# 16_ch_sample-and-hold_card_-_2.net
KiCad netlist of a schematic drawn in EAGLE
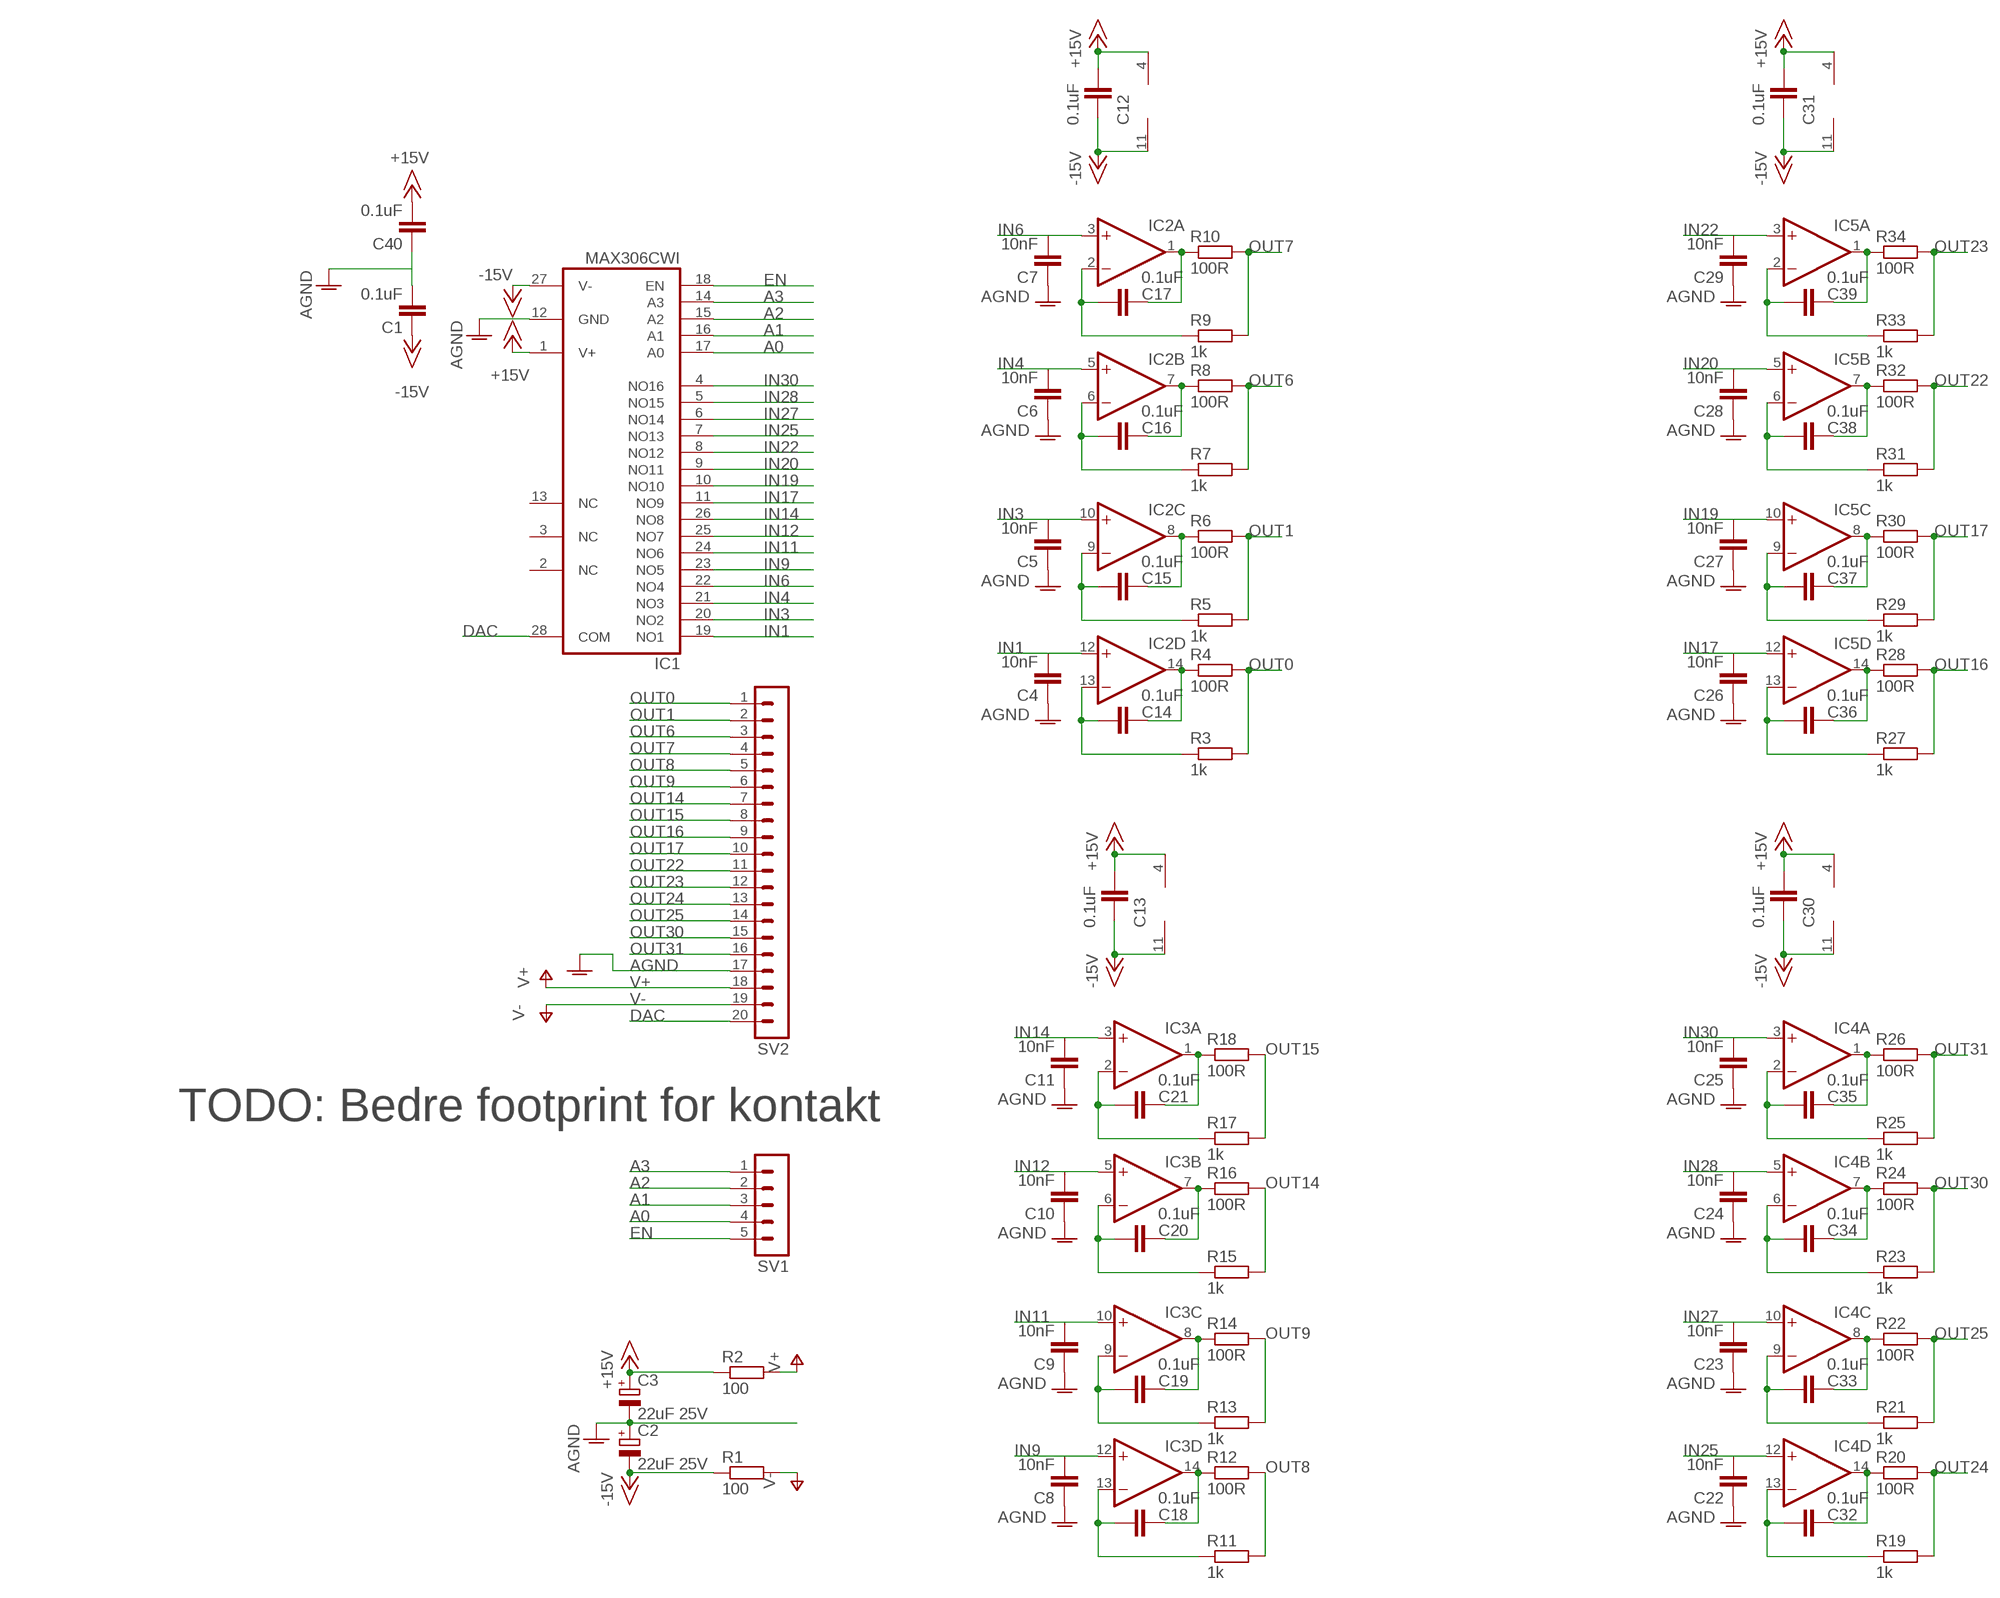
[diagram p0: schematic, sheet 1]

(export (version "E")
  (design (tool "Eeschema 10.0.6"))
  (components
    (comp (ref "C1")
      (value "0.1uF")
      (footprint "eagle-import:C0603")
      (libsource (lib "eagle-import") (part "C-EUC0603"))
    )
    (comp (ref "C2")
      (value "22uF 25V")
      (footprint "eagle-import:E2-5")
      (libsource (lib "eagle-import") (part "CPOL-EUE2-5"))
    )
    (comp (ref "C3")
      (value "22uF 25V")
      (footprint "eagle-import:E2-5")
      (libsource (lib "eagle-import") (part "CPOL-EUE2-5"))
    )
    (comp (ref "C4")
      (value "10nF")
      (footprint "eagle-import:C1206")
      (libsource (lib "eagle-import") (part "C-EUC1206"))
    )
    (comp (ref "C5")
      (value "10nF")
      (footprint "eagle-import:C1206")
      (libsource (lib "eagle-import") (part "C-EUC1206"))
    )
    (comp (ref "C6")
      (value "10nF")
      (footprint "eagle-import:C1206")
      (libsource (lib "eagle-import") (part "C-EUC1206"))
    )
    (comp (ref "C7")
      (value "10nF")
      (footprint "eagle-import:C1206")
      (libsource (lib "eagle-import") (part "C-EUC1206"))
    )
    (comp (ref "C8")
      (value "10nF")
      (footprint "eagle-import:C1206")
      (libsource (lib "eagle-import") (part "C-EUC1206"))
    )
    (comp (ref "C9")
      (value "10nF")
      (footprint "eagle-import:C1206")
      (libsource (lib "eagle-import") (part "C-EUC1206"))
    )
    (comp (ref "C10")
      (value "10nF")
      (footprint "eagle-import:C1206")
      (libsource (lib "eagle-import") (part "C-EUC1206"))
    )
    (comp (ref "C11")
      (value "10nF")
      (footprint "eagle-import:C1206")
      (libsource (lib "eagle-import") (part "C-EUC1206"))
    )
    (comp (ref "C12")
      (value "0.1uF")
      (footprint "eagle-import:C0603")
      (libsource (lib "eagle-import") (part "C-EUC0603"))
    )
    (comp (ref "C13")
      (value "0.1uF")
      (footprint "eagle-import:C0603")
      (libsource (lib "eagle-import") (part "C-EUC0603"))
    )
    (comp (ref "C14")
      (value "0.1uF")
      (footprint "eagle-import:C0603")
      (libsource (lib "eagle-import") (part "C-EUC0603"))
    )
    (comp (ref "C15")
      (value "0.1uF")
      (footprint "eagle-import:C0603")
      (libsource (lib "eagle-import") (part "C-EUC0603"))
    )
    (comp (ref "C16")
      (value "0.1uF")
      (footprint "eagle-import:C0603")
      (libsource (lib "eagle-import") (part "C-EUC0603"))
    )
    (comp (ref "C17")
      (value "0.1uF")
      (footprint "eagle-import:C0603")
      (libsource (lib "eagle-import") (part "C-EUC0603"))
    )
    (comp (ref "C18")
      (value "0.1uF")
      (footprint "eagle-import:C0603")
      (libsource (lib "eagle-import") (part "C-EUC0603"))
    )
    (comp (ref "C19")
      (value "0.1uF")
      (footprint "eagle-import:C0603")
      (libsource (lib "eagle-import") (part "C-EUC0603"))
    )
    (comp (ref "C20")
      (value "0.1uF")
      (footprint "eagle-import:C0603")
      (libsource (lib "eagle-import") (part "C-EUC0603"))
    )
    (comp (ref "C21")
      (value "0.1uF")
      (footprint "eagle-import:C0603")
      (libsource (lib "eagle-import") (part "C-EUC0603"))
    )
    (comp (ref "C22")
      (value "10nF")
      (footprint "eagle-import:C1206")
      (libsource (lib "eagle-import") (part "C-EUC1206"))
    )
    (comp (ref "C23")
      (value "10nF")
      (footprint "eagle-import:C1206")
      (libsource (lib "eagle-import") (part "C-EUC1206"))
    )
    (comp (ref "C24")
      (value "10nF")
      (footprint "eagle-import:C1206")
      (libsource (lib "eagle-import") (part "C-EUC1206"))
    )
    (comp (ref "C25")
      (value "10nF")
      (footprint "eagle-import:C1206")
      (libsource (lib "eagle-import") (part "C-EUC1206"))
    )
    (comp (ref "C26")
      (value "10nF")
      (footprint "eagle-import:C1206")
      (libsource (lib "eagle-import") (part "C-EUC1206"))
    )
    (comp (ref "C27")
      (value "10nF")
      (footprint "eagle-import:C1206")
      (libsource (lib "eagle-import") (part "C-EUC1206"))
    )
    (comp (ref "C28")
      (value "10nF")
      (footprint "eagle-import:C1206")
      (libsource (lib "eagle-import") (part "C-EUC1206"))
    )
    (comp (ref "C29")
      (value "10nF")
      (footprint "eagle-import:C1206")
      (libsource (lib "eagle-import") (part "C-EUC1206"))
    )
    (comp (ref "C30")
      (value "0.1uF")
      (footprint "eagle-import:C0603")
      (libsource (lib "eagle-import") (part "C-EUC0603"))
    )
    (comp (ref "C31")
      (value "0.1uF")
      (footprint "eagle-import:C0603")
      (libsource (lib "eagle-import") (part "C-EUC0603"))
    )
    (comp (ref "C32")
      (value "0.1uF")
      (footprint "eagle-import:C0603")
      (libsource (lib "eagle-import") (part "C-EUC0603"))
    )
    (comp (ref "C33")
      (value "0.1uF")
      (footprint "eagle-import:C0603")
      (libsource (lib "eagle-import") (part "C-EUC0603"))
    )
    (comp (ref "C34")
      (value "0.1uF")
      (footprint "eagle-import:C0603")
      (libsource (lib "eagle-import") (part "C-EUC0603"))
    )
    (comp (ref "C35")
      (value "0.1uF")
      (footprint "eagle-import:C0603")
      (libsource (lib "eagle-import") (part "C-EUC0603"))
    )
    (comp (ref "C36")
      (value "0.1uF")
      (footprint "eagle-import:C0603")
      (libsource (lib "eagle-import") (part "C-EUC0603"))
    )
    (comp (ref "C37")
      (value "0.1uF")
      (footprint "eagle-import:C0603")
      (libsource (lib "eagle-import") (part "C-EUC0603"))
    )
    (comp (ref "C38")
      (value "0.1uF")
      (footprint "eagle-import:C0603")
      (libsource (lib "eagle-import") (part "C-EUC0603"))
    )
    (comp (ref "C39")
      (value "0.1uF")
      (footprint "eagle-import:C0603")
      (libsource (lib "eagle-import") (part "C-EUC0603"))
    )
    (comp (ref "C40")
      (value "0.1uF")
      (footprint "eagle-import:C0603")
      (libsource (lib "eagle-import") (part "C-EUC0603"))
    )
    (comp (ref "IC1")
      (value "MAX306CWI")
      (footprint "eagle-import:SO28L")
      (fields (field (name "MF") "MAXIM"))
      (libsource (lib "eagle-import") (part "MAX306CWI"))
    )
    (comp (ref "IC2")
      (value "TL074D")
      (footprint "eagle-import:SO14")
      (libsource (lib "eagle-import") (part "TL074D"))
    )
    (comp (ref "IC3")
      (value "TL074D")
      (footprint "eagle-import:SO14")
      (libsource (lib "eagle-import") (part "TL074D"))
    )
    (comp (ref "IC4")
      (value "TL074D")
      (footprint "eagle-import:SO14")
      (libsource (lib "eagle-import") (part "TL074D"))
    )
    (comp (ref "IC5")
      (value "TL074D")
      (footprint "eagle-import:SO14")
      (libsource (lib "eagle-import") (part "TL074D"))
    )
    (comp (ref "R1")
      (value "100")
      (footprint "eagle-import:0207_7")
      (libsource (lib "eagle-import") (part "R-EU_0207/7"))
    )
    (comp (ref "R2")
      (value "100")
      (footprint "eagle-import:0207_7")
      (libsource (lib "eagle-import") (part "R-EU_0207/7"))
    )
    (comp (ref "R3")
      (value "1k")
      (footprint "eagle-import:R0603")
      (libsource (lib "eagle-import") (part "R-EU_R0603"))
    )
    (comp (ref "R4")
      (value "100R")
      (footprint "eagle-import:R0603")
      (libsource (lib "eagle-import") (part "R-EU_R0603"))
    )
    (comp (ref "R5")
      (value "1k")
      (footprint "eagle-import:R0603")
      (libsource (lib "eagle-import") (part "R-EU_R0603"))
    )
    (comp (ref "R6")
      (value "100R")
      (footprint "eagle-import:R0603")
      (libsource (lib "eagle-import") (part "R-EU_R0603"))
    )
    (comp (ref "R7")
      (value "1k")
      (footprint "eagle-import:R0603")
      (libsource (lib "eagle-import") (part "R-EU_R0603"))
    )
    (comp (ref "R8")
      (value "100R")
      (footprint "eagle-import:R0603")
      (libsource (lib "eagle-import") (part "R-EU_R0603"))
    )
    (comp (ref "R9")
      (value "1k")
      (footprint "eagle-import:R0603")
      (libsource (lib "eagle-import") (part "R-EU_R0603"))
    )
    (comp (ref "R10")
      (value "100R")
      (footprint "eagle-import:R0603")
      (libsource (lib "eagle-import") (part "R-EU_R0603"))
    )
    (comp (ref "R11")
      (value "1k")
      (footprint "eagle-import:R0603")
      (libsource (lib "eagle-import") (part "R-EU_R0603"))
    )
    (comp (ref "R12")
      (value "100R")
      (footprint "eagle-import:R0603")
      (libsource (lib "eagle-import") (part "R-EU_R0603"))
    )
    (comp (ref "R13")
      (value "1k")
      (footprint "eagle-import:R0603")
      (libsource (lib "eagle-import") (part "R-EU_R0603"))
    )
    (comp (ref "R14")
      (value "100R")
      (footprint "eagle-import:R0603")
      (libsource (lib "eagle-import") (part "R-EU_R0603"))
    )
    (comp (ref "R15")
      (value "1k")
      (footprint "eagle-import:R0603")
      (libsource (lib "eagle-import") (part "R-EU_R0603"))
    )
    (comp (ref "R16")
      (value "100R")
      (footprint "eagle-import:R0603")
      (libsource (lib "eagle-import") (part "R-EU_R0603"))
    )
    (comp (ref "R17")
      (value "1k")
      (footprint "eagle-import:R0603")
      (libsource (lib "eagle-import") (part "R-EU_R0603"))
    )
    (comp (ref "R18")
      (value "100R")
      (footprint "eagle-import:R0603")
      (libsource (lib "eagle-import") (part "R-EU_R0603"))
    )
    (comp (ref "R19")
      (value "1k")
      (footprint "eagle-import:R0603")
      (libsource (lib "eagle-import") (part "R-EU_R0603"))
    )
    (comp (ref "R20")
      (value "100R")
      (footprint "eagle-import:R0603")
      (libsource (lib "eagle-import") (part "R-EU_R0603"))
    )
    (comp (ref "R21")
      (value "1k")
      (footprint "eagle-import:R0603")
      (libsource (lib "eagle-import") (part "R-EU_R0603"))
    )
    (comp (ref "R22")
      (value "100R")
      (footprint "eagle-import:R0603")
      (libsource (lib "eagle-import") (part "R-EU_R0603"))
    )
    (comp (ref "R23")
      (value "1k")
      (footprint "eagle-import:R0603")
      (libsource (lib "eagle-import") (part "R-EU_R0603"))
    )
    (comp (ref "R24")
      (value "100R")
      (footprint "eagle-import:R0603")
      (libsource (lib "eagle-import") (part "R-EU_R0603"))
    )
    (comp (ref "R25")
      (value "1k")
      (footprint "eagle-import:R0603")
      (libsource (lib "eagle-import") (part "R-EU_R0603"))
    )
    (comp (ref "R26")
      (value "100R")
      (footprint "eagle-import:R0603")
      (libsource (lib "eagle-import") (part "R-EU_R0603"))
    )
    (comp (ref "R27")
      (value "1k")
      (footprint "eagle-import:R0603")
      (libsource (lib "eagle-import") (part "R-EU_R0603"))
    )
    (comp (ref "R28")
      (value "100R")
      (footprint "eagle-import:R0603")
      (libsource (lib "eagle-import") (part "R-EU_R0603"))
    )
    (comp (ref "R29")
      (value "1k")
      (footprint "eagle-import:R0603")
      (libsource (lib "eagle-import") (part "R-EU_R0603"))
    )
    (comp (ref "R30")
      (value "100R")
      (footprint "eagle-import:R0603")
      (libsource (lib "eagle-import") (part "R-EU_R0603"))
    )
    (comp (ref "R31")
      (value "1k")
      (footprint "eagle-import:R0603")
      (libsource (lib "eagle-import") (part "R-EU_R0603"))
    )
    (comp (ref "R32")
      (value "100R")
      (footprint "eagle-import:R0603")
      (libsource (lib "eagle-import") (part "R-EU_R0603"))
    )
    (comp (ref "R33")
      (value "1k")
      (footprint "eagle-import:R0603")
      (libsource (lib "eagle-import") (part "R-EU_R0603"))
    )
    (comp (ref "R34")
      (value "100R")
      (footprint "eagle-import:R0603")
      (libsource (lib "eagle-import") (part "R-EU_R0603"))
    )
    (comp (ref "SV1")
      (value "MA05-1")
      (footprint "eagle-import:MA05-1")
      (libsource (lib "eagle-import") (part "MA05-1"))
    )
    (comp (ref "SV2")
      (value "MA20-1")
      (footprint "eagle-import:MA20-1")
      (libsource (lib "eagle-import") (part "MA20-1"))
    )
  )
  (nets
    (net (code "1") (name "+15V") (class "Default")
      (node (ref "C12") (pin "1") (pinfunction "1_1") (pintype "passive"))
      (node (ref "C13") (pin "1") (pinfunction "1_1") (pintype "passive"))
      (node (ref "C3") (pin "+") (pinfunction "+_+") (pintype "passive"))
      (node (ref "C30") (pin "1") (pinfunction "1_1") (pintype "passive"))
      (node (ref "C31") (pin "1") (pinfunction "1_1") (pintype "passive"))
      (node (ref "C40") (pin "2") (pinfunction "2_2") (pintype "passive"))
      (node (ref "IC1") (pin "1") (pinfunction "V+_1") (pintype "power_in"))
      (node (ref "IC2") (pin "4") (pinfunction "V+_4") (pintype "power_in"))
      (node (ref "IC3") (pin "4") (pinfunction "V+_4") (pintype "power_in"))
      (node (ref "IC4") (pin "4") (pinfunction "V+_4") (pintype "power_in"))
      (node (ref "IC5") (pin "4") (pinfunction "V+_4") (pintype "power_in"))
      (node (ref "R2") (pin "1") (pinfunction "1_1") (pintype "passive"))
    )
    (net (code "2") (name "-15V") (class "Default")
      (node (ref "C1") (pin "1") (pinfunction "1_1") (pintype "passive"))
      (node (ref "C12") (pin "2") (pinfunction "2_2") (pintype "passive"))
      (node (ref "C13") (pin "2") (pinfunction "2_2") (pintype "passive"))
      (node (ref "C2") (pin "-") (pinfunction "-_-") (pintype "passive"))
      (node (ref "C30") (pin "2") (pinfunction "2_2") (pintype "passive"))
      (node (ref "C31") (pin "2") (pinfunction "2_2") (pintype "passive"))
      (node (ref "IC1") (pin "27") (pinfunction "V-_27") (pintype "power_in"))
      (node (ref "IC2") (pin "11") (pinfunction "V-_11") (pintype "power_in"))
      (node (ref "IC3") (pin "11") (pinfunction "V-_11") (pintype "power_in"))
      (node (ref "IC4") (pin "11") (pinfunction "V-_11") (pintype "power_in"))
      (node (ref "IC5") (pin "11") (pinfunction "V-_11") (pintype "power_in"))
      (node (ref "R1") (pin "1") (pinfunction "1_1") (pintype "passive"))
    )
    (net (code "3") (name "/A0") (class "Default")
      (node (ref "IC1") (pin "17") (pinfunction "A0_17") (pintype "input"))
      (node (ref "SV1") (pin "4") (pinfunction "4_4") (pintype "passive"))
    )
    (net (code "4") (name "/A1") (class "Default")
      (node (ref "IC1") (pin "16") (pinfunction "A1_16") (pintype "input"))
      (node (ref "SV1") (pin "3") (pinfunction "3_3") (pintype "passive"))
    )
    (net (code "5") (name "/A2") (class "Default")
      (node (ref "IC1") (pin "15") (pinfunction "A2_15") (pintype "input"))
      (node (ref "SV1") (pin "2") (pinfunction "2_2") (pintype "passive"))
    )
    (net (code "6") (name "/A3") (class "Default")
      (node (ref "IC1") (pin "14") (pinfunction "A3_14") (pintype "input"))
      (node (ref "SV1") (pin "1") (pinfunction "1_1") (pintype "passive"))
    )
    (net (code "7") (name "/DAC") (class "Default")
      (node (ref "IC1") (pin "28") (pinfunction "COM_28") (pintype "passive"))
      (node (ref "SV2") (pin "20") (pinfunction "20_20") (pintype "passive"))
    )
    (net (code "8") (name "/EN") (class "Default")
      (node (ref "IC1") (pin "18") (pinfunction "EN_18") (pintype "input"))
      (node (ref "SV1") (pin "5") (pinfunction "5_5") (pintype "passive"))
    )
    (net (code "9") (name "/IN1") (class "Default")
      (node (ref "C4") (pin "2") (pinfunction "2_2") (pintype "passive"))
      (node (ref "IC1") (pin "19") (pinfunction "NO1_19") (pintype "passive"))
      (node (ref "IC2") (pin "12") (pinfunction "+IN_12") (pintype "input"))
    )
    (net (code "10") (name "/IN3") (class "Default")
      (node (ref "C5") (pin "2") (pinfunction "2_2") (pintype "passive"))
      (node (ref "IC1") (pin "20") (pinfunction "NO2_20") (pintype "passive"))
      (node (ref "IC2") (pin "10") (pinfunction "+IN_10") (pintype "input"))
    )
    (net (code "11") (name "/IN4") (class "Default")
      (node (ref "C6") (pin "2") (pinfunction "2_2") (pintype "passive"))
      (node (ref "IC1") (pin "21") (pinfunction "NO3_21") (pintype "passive"))
      (node (ref "IC2") (pin "5") (pinfunction "+IN_5") (pintype "input"))
    )
    (net (code "12") (name "/IN6") (class "Default")
      (node (ref "C7") (pin "2") (pinfunction "2_2") (pintype "passive"))
      (node (ref "IC1") (pin "22") (pinfunction "NO4_22") (pintype "passive"))
      (node (ref "IC2") (pin "3") (pinfunction "+IN_3") (pintype "input"))
    )
    (net (code "13") (name "/IN9") (class "Default")
      (node (ref "C8") (pin "2") (pinfunction "2_2") (pintype "passive"))
      (node (ref "IC1") (pin "23") (pinfunction "NO5_23") (pintype "passive"))
      (node (ref "IC3") (pin "12") (pinfunction "+IN_12") (pintype "input"))
    )
    (net (code "14") (name "/IN11") (class "Default")
      (node (ref "C9") (pin "2") (pinfunction "2_2") (pintype "passive"))
      (node (ref "IC1") (pin "24") (pinfunction "NO6_24") (pintype "passive"))
      (node (ref "IC3") (pin "10") (pinfunction "+IN_10") (pintype "input"))
    )
    (net (code "15") (name "/IN12") (class "Default")
      (node (ref "C10") (pin "2") (pinfunction "2_2") (pintype "passive"))
      (node (ref "IC1") (pin "25") (pinfunction "NO7_25") (pintype "passive"))
      (node (ref "IC3") (pin "5") (pinfunction "+IN_5") (pintype "input"))
    )
    (net (code "16") (name "/IN14") (class "Default")
      (node (ref "C11") (pin "2") (pinfunction "2_2") (pintype "passive"))
      (node (ref "IC1") (pin "26") (pinfunction "NO8_26") (pintype "passive"))
      (node (ref "IC3") (pin "3") (pinfunction "+IN_3") (pintype "input"))
    )
    (net (code "17") (name "/IN17") (class "Default")
      (node (ref "C26") (pin "2") (pinfunction "2_2") (pintype "passive"))
      (node (ref "IC1") (pin "11") (pinfunction "NO9_11") (pintype "passive"))
      (node (ref "IC5") (pin "12") (pinfunction "+IN_12") (pintype "input"))
    )
    (net (code "18") (name "/IN19") (class "Default")
      (node (ref "C27") (pin "2") (pinfunction "2_2") (pintype "passive"))
      (node (ref "IC1") (pin "10") (pinfunction "NO10_10") (pintype "passive"))
      (node (ref "IC5") (pin "10") (pinfunction "+IN_10") (pintype "input"))
    )
    (net (code "19") (name "/IN20") (class "Default")
      (node (ref "C28") (pin "2") (pinfunction "2_2") (pintype "passive"))
      (node (ref "IC1") (pin "9") (pinfunction "NO11_9") (pintype "passive"))
      (node (ref "IC5") (pin "5") (pinfunction "+IN_5") (pintype "input"))
    )
    (net (code "20") (name "/IN22") (class "Default")
      (node (ref "C29") (pin "2") (pinfunction "2_2") (pintype "passive"))
      (node (ref "IC1") (pin "8") (pinfunction "NO12_8") (pintype "passive"))
      (node (ref "IC5") (pin "3") (pinfunction "+IN_3") (pintype "input"))
    )
    (net (code "21") (name "/IN25") (class "Default")
      (node (ref "C22") (pin "2") (pinfunction "2_2") (pintype "passive"))
      (node (ref "IC1") (pin "7") (pinfunction "NO13_7") (pintype "passive"))
      (node (ref "IC4") (pin "12") (pinfunction "+IN_12") (pintype "input"))
    )
    (net (code "22") (name "/IN27") (class "Default")
      (node (ref "C23") (pin "2") (pinfunction "2_2") (pintype "passive"))
      (node (ref "IC1") (pin "6") (pinfunction "NO14_6") (pintype "passive"))
      (node (ref "IC4") (pin "10") (pinfunction "+IN_10") (pintype "input"))
    )
    (net (code "23") (name "/IN28") (class "Default")
      (node (ref "C24") (pin "2") (pinfunction "2_2") (pintype "passive"))
      (node (ref "IC1") (pin "5") (pinfunction "NO15_5") (pintype "passive"))
      (node (ref "IC4") (pin "5") (pinfunction "+IN_5") (pintype "input"))
    )
    (net (code "24") (name "/IN30") (class "Default")
      (node (ref "C25") (pin "2") (pinfunction "2_2") (pintype "passive"))
      (node (ref "IC1") (pin "4") (pinfunction "NO16_4") (pintype "passive"))
      (node (ref "IC4") (pin "3") (pinfunction "+IN_3") (pintype "input"))
    )
    (net (code "25") (name "/OUT0") (class "Default")
      (node (ref "R3") (pin "2") (pinfunction "2_2") (pintype "passive"))
      (node (ref "R4") (pin "2") (pinfunction "2_2") (pintype "passive"))
      (node (ref "SV2") (pin "1") (pinfunction "1_1") (pintype "passive"))
    )
    (net (code "26") (name "/OUT1") (class "Default")
      (node (ref "R5") (pin "2") (pinfunction "2_2") (pintype "passive"))
      (node (ref "R6") (pin "2") (pinfunction "2_2") (pintype "passive"))
      (node (ref "SV2") (pin "2") (pinfunction "2_2") (pintype "passive"))
    )
    (net (code "27") (name "/OUT6") (class "Default")
      (node (ref "R7") (pin "2") (pinfunction "2_2") (pintype "passive"))
      (node (ref "R8") (pin "2") (pinfunction "2_2") (pintype "passive"))
      (node (ref "SV2") (pin "3") (pinfunction "3_3") (pintype "passive"))
    )
    (net (code "28") (name "/OUT7") (class "Default")
      (node (ref "R10") (pin "2") (pinfunction "2_2") (pintype "passive"))
      (node (ref "R9") (pin "2") (pinfunction "2_2") (pintype "passive"))
      (node (ref "SV2") (pin "4") (pinfunction "4_4") (pintype "passive"))
    )
    (net (code "29") (name "/OUT8") (class "Default")
      (node (ref "R11") (pin "2") (pinfunction "2_2") (pintype "passive"))
      (node (ref "R12") (pin "2") (pinfunction "2_2") (pintype "passive"))
      (node (ref "SV2") (pin "5") (pinfunction "5_5") (pintype "passive"))
    )
    (net (code "30") (name "/OUT9") (class "Default")
      (node (ref "R13") (pin "2") (pinfunction "2_2") (pintype "passive"))
      (node (ref "R14") (pin "2") (pinfunction "2_2") (pintype "passive"))
      (node (ref "SV2") (pin "6") (pinfunction "6_6") (pintype "passive"))
    )
    (net (code "31") (name "/OUT14") (class "Default")
      (node (ref "R15") (pin "2") (pinfunction "2_2") (pintype "passive"))
      (node (ref "R16") (pin "2") (pinfunction "2_2") (pintype "passive"))
      (node (ref "SV2") (pin "7") (pinfunction "7_7") (pintype "passive"))
    )
    (net (code "32") (name "/OUT15") (class "Default")
      (node (ref "R17") (pin "2") (pinfunction "2_2") (pintype "passive"))
      (node (ref "R18") (pin "2") (pinfunction "2_2") (pintype "passive"))
      (node (ref "SV2") (pin "8") (pinfunction "8_8") (pintype "passive"))
    )
    (net (code "33") (name "/OUT16") (class "Default")
      (node (ref "R27") (pin "2") (pinfunction "2_2") (pintype "passive"))
      (node (ref "R28") (pin "2") (pinfunction "2_2") (pintype "passive"))
      (node (ref "SV2") (pin "9") (pinfunction "9_9") (pintype "passive"))
    )
    (net (code "34") (name "/OUT17") (class "Default")
      (node (ref "R29") (pin "2") (pinfunction "2_2") (pintype "passive"))
      (node (ref "R30") (pin "2") (pinfunction "2_2") (pintype "passive"))
      (node (ref "SV2") (pin "10") (pinfunction "10_10") (pintype "passive"))
    )
    (net (code "35") (name "/OUT22") (class "Default")
      (node (ref "R31") (pin "2") (pinfunction "2_2") (pintype "passive"))
      (node (ref "R32") (pin "2") (pinfunction "2_2") (pintype "passive"))
      (node (ref "SV2") (pin "11") (pinfunction "11_11") (pintype "passive"))
    )
    (net (code "36") (name "/OUT23") (class "Default")
      (node (ref "R33") (pin "2") (pinfunction "2_2") (pintype "passive"))
      (node (ref "R34") (pin "2") (pinfunction "2_2") (pintype "passive"))
      (node (ref "SV2") (pin "12") (pinfunction "12_12") (pintype "passive"))
    )
    (net (code "37") (name "/OUT24") (class "Default")
      (node (ref "R19") (pin "2") (pinfunction "2_2") (pintype "passive"))
      (node (ref "R20") (pin "2") (pinfunction "2_2") (pintype "passive"))
      (node (ref "SV2") (pin "13") (pinfunction "13_13") (pintype "passive"))
    )
    (net (code "38") (name "/OUT25") (class "Default")
      (node (ref "R21") (pin "2") (pinfunction "2_2") (pintype "passive"))
      (node (ref "R22") (pin "2") (pinfunction "2_2") (pintype "passive"))
      (node (ref "SV2") (pin "14") (pinfunction "14_14") (pintype "passive"))
    )
    (net (code "39") (name "/OUT30") (class "Default")
      (node (ref "R23") (pin "2") (pinfunction "2_2") (pintype "passive"))
      (node (ref "R24") (pin "2") (pinfunction "2_2") (pintype "passive"))
      (node (ref "SV2") (pin "15") (pinfunction "15_15") (pintype "passive"))
    )
    (net (code "40") (name "/OUT31") (class "Default")
      (node (ref "R25") (pin "2") (pinfunction "2_2") (pintype "passive"))
      (node (ref "R26") (pin "2") (pinfunction "2_2") (pintype "passive"))
      (node (ref "SV2") (pin "16") (pinfunction "16_16") (pintype "passive"))
    )
    (net (code "41") (name "AGND") (class "Default")
      (node (ref "C1") (pin "2") (pinfunction "2_2") (pintype "passive"))
      (node (ref "C10") (pin "1") (pinfunction "1_1") (pintype "passive"))
      (node (ref "C11") (pin "1") (pinfunction "1_1") (pintype "passive"))
      (node (ref "C2") (pin "+") (pinfunction "+_+") (pintype "passive"))
      (node (ref "C22") (pin "1") (pinfunction "1_1") (pintype "passive"))
      (node (ref "C23") (pin "1") (pinfunction "1_1") (pintype "passive"))
      (node (ref "C24") (pin "1") (pinfunction "1_1") (pintype "passive"))
      (node (ref "C25") (pin "1") (pinfunction "1_1") (pintype "passive"))
      (node (ref "C26") (pin "1") (pinfunction "1_1") (pintype "passive"))
      (node (ref "C27") (pin "1") (pinfunction "1_1") (pintype "passive"))
      (node (ref "C28") (pin "1") (pinfunction "1_1") (pintype "passive"))
      (node (ref "C29") (pin "1") (pinfunction "1_1") (pintype "passive"))
      (node (ref "C3") (pin "-") (pinfunction "-_-") (pintype "passive"))
      (node (ref "C4") (pin "1") (pinfunction "1_1") (pintype "passive"))
      (node (ref "C40") (pin "1") (pinfunction "1_1") (pintype "passive"))
      (node (ref "C5") (pin "1") (pinfunction "1_1") (pintype "passive"))
      (node (ref "C6") (pin "1") (pinfunction "1_1") (pintype "passive"))
      (node (ref "C7") (pin "1") (pinfunction "1_1") (pintype "passive"))
      (node (ref "C8") (pin "1") (pinfunction "1_1") (pintype "passive"))
      (node (ref "C9") (pin "1") (pinfunction "1_1") (pintype "passive"))
      (node (ref "IC1") (pin "12") (pinfunction "GND_12") (pintype "power_in"))
      (node (ref "SV2") (pin "17") (pinfunction "17_17") (pintype "passive"))
    )
    (net (code "42") (name "Net-(IC2A--IN)") (class "Default")
      (node (ref "C17") (pin "2") (pinfunction "2_2") (pintype "passive"))
      (node (ref "IC2") (pin "2") (pinfunction "-IN_2") (pintype "input"))
      (node (ref "R9") (pin "1") (pinfunction "1_1") (pintype "passive"))
    )
    (net (code "43") (name "Net-(IC2A-OUT)") (class "Default")
      (node (ref "C17") (pin "1") (pinfunction "1_1") (pintype "passive"))
      (node (ref "IC2") (pin "1") (pinfunction "OUT_1") (pintype "output"))
      (node (ref "R10") (pin "1") (pinfunction "1_1") (pintype "passive"))
    )
    (net (code "44") (name "Net-(IC2B--IN)") (class "Default")
      (node (ref "C16") (pin "2") (pinfunction "2_2") (pintype "passive"))
      (node (ref "IC2") (pin "6") (pinfunction "-IN_6") (pintype "input"))
      (node (ref "R7") (pin "1") (pinfunction "1_1") (pintype "passive"))
    )
    (net (code "45") (name "Net-(IC2B-OUT)") (class "Default")
      (node (ref "C16") (pin "1") (pinfunction "1_1") (pintype "passive"))
      (node (ref "IC2") (pin "7") (pinfunction "OUT_7") (pintype "output"))
      (node (ref "R8") (pin "1") (pinfunction "1_1") (pintype "passive"))
    )
    (net (code "46") (name "Net-(IC2C--IN)") (class "Default")
      (node (ref "C15") (pin "2") (pinfunction "2_2") (pintype "passive"))
      (node (ref "IC2") (pin "9") (pinfunction "-IN_9") (pintype "input"))
      (node (ref "R5") (pin "1") (pinfunction "1_1") (pintype "passive"))
    )
    (net (code "47") (name "Net-(IC2C-OUT)") (class "Default")
      (node (ref "C15") (pin "1") (pinfunction "1_1") (pintype "passive"))
      (node (ref "IC2") (pin "8") (pinfunction "OUT_8") (pintype "output"))
      (node (ref "R6") (pin "1") (pinfunction "1_1") (pintype "passive"))
    )
    (net (code "48") (name "Net-(IC2D--IN)") (class "Default")
      (node (ref "C14") (pin "2") (pinfunction "2_2") (pintype "passive"))
      (node (ref "IC2") (pin "13") (pinfunction "-IN_13") (pintype "input"))
      (node (ref "R3") (pin "1") (pinfunction "1_1") (pintype "passive"))
    )
    (net (code "49") (name "Net-(IC2D-OUT)") (class "Default")
      (node (ref "C14") (pin "1") (pinfunction "1_1") (pintype "passive"))
      (node (ref "IC2") (pin "14") (pinfunction "OUT_14") (pintype "output"))
      (node (ref "R4") (pin "1") (pinfunction "1_1") (pintype "passive"))
    )
    (net (code "50") (name "Net-(IC3A--IN)") (class "Default")
      (node (ref "C21") (pin "2") (pinfunction "2_2") (pintype "passive"))
      (node (ref "IC3") (pin "2") (pinfunction "-IN_2") (pintype "input"))
      (node (ref "R17") (pin "1") (pinfunction "1_1") (pintype "passive"))
    )
    (net (code "51") (name "Net-(IC3A-OUT)") (class "Default")
      (node (ref "C21") (pin "1") (pinfunction "1_1") (pintype "passive"))
      (node (ref "IC3") (pin "1") (pinfunction "OUT_1") (pintype "output"))
      (node (ref "R18") (pin "1") (pinfunction "1_1") (pintype "passive"))
    )
    (net (code "52") (name "Net-(IC3B--IN)") (class "Default")
      (node (ref "C20") (pin "2") (pinfunction "2_2") (pintype "passive"))
      (node (ref "IC3") (pin "6") (pinfunction "-IN_6") (pintype "input"))
      (node (ref "R15") (pin "1") (pinfunction "1_1") (pintype "passive"))
    )
    (net (code "53") (name "Net-(IC3B-OUT)") (class "Default")
      (node (ref "C20") (pin "1") (pinfunction "1_1") (pintype "passive"))
      (node (ref "IC3") (pin "7") (pinfunction "OUT_7") (pintype "output"))
      (node (ref "R16") (pin "1") (pinfunction "1_1") (pintype "passive"))
    )
    (net (code "54") (name "Net-(IC3C--IN)") (class "Default")
      (node (ref "C19") (pin "2") (pinfunction "2_2") (pintype "passive"))
      (node (ref "IC3") (pin "9") (pinfunction "-IN_9") (pintype "input"))
      (node (ref "R13") (pin "1") (pinfunction "1_1") (pintype "passive"))
    )
    (net (code "55") (name "Net-(IC3C-OUT)") (class "Default")
      (node (ref "C19") (pin "1") (pinfunction "1_1") (pintype "passive"))
      (node (ref "IC3") (pin "8") (pinfunction "OUT_8") (pintype "output"))
      (node (ref "R14") (pin "1") (pinfunction "1_1") (pintype "passive"))
    )
    (net (code "56") (name "Net-(IC3D--IN)") (class "Default")
      (node (ref "C18") (pin "2") (pinfunction "2_2") (pintype "passive"))
      (node (ref "IC3") (pin "13") (pinfunction "-IN_13") (pintype "input"))
      (node (ref "R11") (pin "1") (pinfunction "1_1") (pintype "passive"))
    )
    (net (code "57") (name "Net-(IC3D-OUT)") (class "Default")
      (node (ref "C18") (pin "1") (pinfunction "1_1") (pintype "passive"))
      (node (ref "IC3") (pin "14") (pinfunction "OUT_14") (pintype "output"))
      (node (ref "R12") (pin "1") (pinfunction "1_1") (pintype "passive"))
    )
    (net (code "58") (name "Net-(IC4A--IN)") (class "Default")
      (node (ref "C35") (pin "2") (pinfunction "2_2") (pintype "passive"))
      (node (ref "IC4") (pin "2") (pinfunction "-IN_2") (pintype "input"))
      (node (ref "R25") (pin "1") (pinfunction "1_1") (pintype "passive"))
    )
    (net (code "59") (name "Net-(IC4A-OUT)") (class "Default")
      (node (ref "C35") (pin "1") (pinfunction "1_1") (pintype "passive"))
      (node (ref "IC4") (pin "1") (pinfunction "OUT_1") (pintype "output"))
      (node (ref "R26") (pin "1") (pinfunction "1_1") (pintype "passive"))
    )
    (net (code "60") (name "Net-(IC4B--IN)") (class "Default")
      (node (ref "C34") (pin "2") (pinfunction "2_2") (pintype "passive"))
      (node (ref "IC4") (pin "6") (pinfunction "-IN_6") (pintype "input"))
      (node (ref "R23") (pin "1") (pinfunction "1_1") (pintype "passive"))
    )
    (net (code "61") (name "Net-(IC4B-OUT)") (class "Default")
      (node (ref "C34") (pin "1") (pinfunction "1_1") (pintype "passive"))
      (node (ref "IC4") (pin "7") (pinfunction "OUT_7") (pintype "output"))
      (node (ref "R24") (pin "1") (pinfunction "1_1") (pintype "passive"))
    )
    (net (code "62") (name "Net-(IC4C--IN)") (class "Default")
      (node (ref "C33") (pin "2") (pinfunction "2_2") (pintype "passive"))
      (node (ref "IC4") (pin "9") (pinfunction "-IN_9") (pintype "input"))
      (node (ref "R21") (pin "1") (pinfunction "1_1") (pintype "passive"))
    )
    (net (code "63") (name "Net-(IC4C-OUT)") (class "Default")
      (node (ref "C33") (pin "1") (pinfunction "1_1") (pintype "passive"))
      (node (ref "IC4") (pin "8") (pinfunction "OUT_8") (pintype "output"))
      (node (ref "R22") (pin "1") (pinfunction "1_1") (pintype "passive"))
    )
    (net (code "64") (name "Net-(IC4D--IN)") (class "Default")
      (node (ref "C32") (pin "2") (pinfunction "2_2") (pintype "passive"))
      (node (ref "IC4") (pin "13") (pinfunction "-IN_13") (pintype "input"))
      (node (ref "R19") (pin "1") (pinfunction "1_1") (pintype "passive"))
    )
    (net (code "65") (name "Net-(IC4D-OUT)") (class "Default")
      (node (ref "C32") (pin "1") (pinfunction "1_1") (pintype "passive"))
      (node (ref "IC4") (pin "14") (pinfunction "OUT_14") (pintype "output"))
      (node (ref "R20") (pin "1") (pinfunction "1_1") (pintype "passive"))
    )
    (net (code "66") (name "Net-(IC5A--IN)") (class "Default")
      (node (ref "C39") (pin "2") (pinfunction "2_2") (pintype "passive"))
      (node (ref "IC5") (pin "2") (pinfunction "-IN_2") (pintype "input"))
      (node (ref "R33") (pin "1") (pinfunction "1_1") (pintype "passive"))
    )
    (net (code "67") (name "Net-(IC5A-OUT)") (class "Default")
      (node (ref "C39") (pin "1") (pinfunction "1_1") (pintype "passive"))
      (node (ref "IC5") (pin "1") (pinfunction "OUT_1") (pintype "output"))
      (node (ref "R34") (pin "1") (pinfunction "1_1") (pintype "passive"))
    )
    (net (code "68") (name "Net-(IC5B--IN)") (class "Default")
      (node (ref "C38") (pin "2") (pinfunction "2_2") (pintype "passive"))
      (node (ref "IC5") (pin "6") (pinfunction "-IN_6") (pintype "input"))
      (node (ref "R31") (pin "1") (pinfunction "1_1") (pintype "passive"))
    )
    (net (code "69") (name "Net-(IC5B-OUT)") (class "Default")
      (node (ref "C38") (pin "1") (pinfunction "1_1") (pintype "passive"))
      (node (ref "IC5") (pin "7") (pinfunction "OUT_7") (pintype "output"))
      (node (ref "R32") (pin "1") (pinfunction "1_1") (pintype "passive"))
    )
    (net (code "70") (name "Net-(IC5C--IN)") (class "Default")
      (node (ref "C37") (pin "2") (pinfunction "2_2") (pintype "passive"))
      (node (ref "IC5") (pin "9") (pinfunction "-IN_9") (pintype "input"))
      (node (ref "R29") (pin "1") (pinfunction "1_1") (pintype "passive"))
    )
    (net (code "71") (name "Net-(IC5C-OUT)") (class "Default")
      (node (ref "C37") (pin "1") (pinfunction "1_1") (pintype "passive"))
      (node (ref "IC5") (pin "8") (pinfunction "OUT_8") (pintype "output"))
      (node (ref "R30") (pin "1") (pinfunction "1_1") (pintype "passive"))
    )
    (net (code "72") (name "Net-(IC5D--IN)") (class "Default")
      (node (ref "C36") (pin "2") (pinfunction "2_2") (pintype "passive"))
      (node (ref "IC5") (pin "13") (pinfunction "-IN_13") (pintype "input"))
      (node (ref "R27") (pin "1") (pinfunction "1_1") (pintype "passive"))
    )
    (net (code "73") (name "Net-(IC5D-OUT)") (class "Default")
      (node (ref "C36") (pin "1") (pinfunction "1_1") (pintype "passive"))
      (node (ref "IC5") (pin "14") (pinfunction "OUT_14") (pintype "output"))
      (node (ref "R28") (pin "1") (pinfunction "1_1") (pintype "passive"))
    )
    (net (code "74") (name "V+") (class "Default")
      (node (ref "R2") (pin "2") (pinfunction "2_2") (pintype "passive"))
      (node (ref "SV2") (pin "18") (pinfunction "18_18") (pintype "passive"))
    )
    (net (code "75") (name "V-") (class "Default")
      (node (ref "R1") (pin "2") (pinfunction "2_2") (pintype "passive"))
      (node (ref "SV2") (pin "19") (pinfunction "19_19") (pintype "passive"))
    )
    (net (code "76") (name "unconnected-(IC1-NC-Pad2)") (class "Default")
      (node (ref "IC1") (pin "2") (pinfunction "NC_2") (pintype "no_connect"))
    )
    (net (code "77") (name "unconnected-(IC1-NC-Pad3)") (class "Default")
      (node (ref "IC1") (pin "3") (pinfunction "NC_3") (pintype "no_connect"))
    )
    (net (code "78") (name "unconnected-(IC1-NC-Pad13)") (class "Default")
      (node (ref "IC1") (pin "13") (pinfunction "NC_13") (pintype "no_connect"))
    )
  )
)
